# wattcher_to_rpi.net
KiCad netlist of a schematic drawn in EAGLE
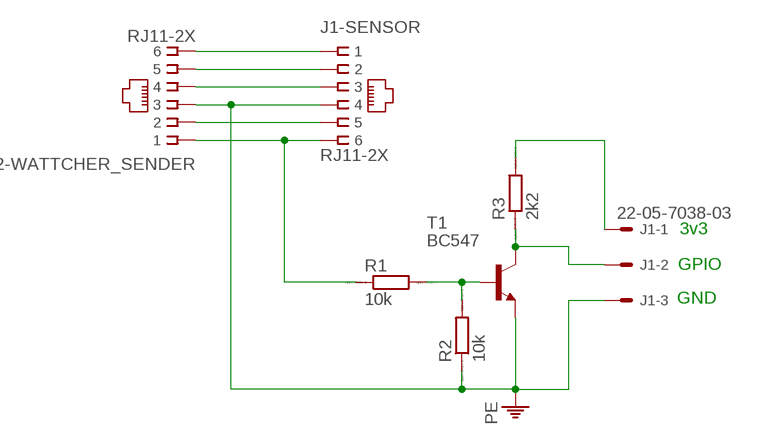
[diagram p0: schematic, sheet 1]

(export (version "E")
  (design (tool "Eeschema 10.0.6"))
  (components
    (comp (ref "J1")
      (value "22-05-7038-03")
      (footprint "eagle-import:7395-03")
      (libsource (lib "eagle-import") (part "22-?-0305-7038"))
    )
    (comp (ref "J1-SENSOR")
      (value "RJ11-2X")
      (footprint "eagle-import:RJ11-NO_SHIELD")
      (libsource (lib "eagle-import") (part "RJ11-2X"))
    )
    (comp (ref "J2-WATTCHER_SENDER")
      (value "RJ11-2X")
      (footprint "eagle-import:RJ11-NO_SHIELD")
      (libsource (lib "eagle-import") (part "RJ11-2X"))
    )
    (comp (ref "R1")
      (value "10k")
      (footprint "eagle-import:0207_7")
      (libsource (lib "eagle-import") (part "R-EU_0207_7"))
    )
    (comp (ref "R2")
      (value "10k")
      (footprint "eagle-import:0207_7")
      (libsource (lib "eagle-import") (part "R-EU_0207_7"))
    )
    (comp (ref "R3")
      (value "2k2")
      (footprint "eagle-import:0207_7")
      (libsource (lib "eagle-import") (part "R-EU_0207_7"))
    )
    (comp (ref "T1")
      (value "BC547")
      (footprint "eagle-import:TO92")
      (libsource (lib "eagle-import") (part "BC547"))
    )
  )
  (nets
    (net (code "1") (name "Net-(J1-SENSOR-Pad1)") (class "Default")
      (node (ref "J1-SENSOR") (pin "1") (pinfunction "1_1") (pintype "passive"))
      (node (ref "J2-WATTCHER_SENDER") (pin "6") (pinfunction "6_6") (pintype "passive"))
    )
    (net (code "2") (name "Net-(J1-SENSOR-Pad2)") (class "Default")
      (node (ref "J1-SENSOR") (pin "2") (pinfunction "2_2") (pintype "passive"))
      (node (ref "J2-WATTCHER_SENDER") (pin "5") (pinfunction "5_5") (pintype "passive"))
    )
    (net (code "3") (name "Net-(J1-SENSOR-Pad3)") (class "Default")
      (node (ref "J1-SENSOR") (pin "3") (pinfunction "3_3") (pintype "passive"))
      (node (ref "J2-WATTCHER_SENDER") (pin "4") (pinfunction "4_4") (pintype "passive"))
    )
    (net (code "4") (name "Net-(J1-SENSOR-Pad5)") (class "Default")
      (node (ref "J1-SENSOR") (pin "5") (pinfunction "5_5") (pintype "passive"))
      (node (ref "J2-WATTCHER_SENDER") (pin "2") (pinfunction "2_2") (pintype "passive"))
    )
    (net (code "5") (name "Net-(J1-SENSOR-Pad6)") (class "Default")
      (node (ref "J1-SENSOR") (pin "6") (pinfunction "6_6") (pintype "passive"))
      (node (ref "J2-WATTCHER_SENDER") (pin "1") (pinfunction "1_1") (pintype "passive"))
      (node (ref "R1") (pin "1") (pinfunction "1_1") (pintype "passive"))
    )
    (net (code "6") (name "Net-(J1A-S)") (class "Default")
      (node (ref "J1") (pin "1") (pinfunction "S_1") (pintype "passive"))
      (node (ref "R3") (pin "2") (pinfunction "2_2") (pintype "passive"))
    )
    (net (code "7") (name "Net-(J1B-S)") (class "Default")
      (node (ref "J1") (pin "2") (pinfunction "S_2") (pintype "passive"))
      (node (ref "R3") (pin "1") (pinfunction "1_1") (pintype "passive"))
      (node (ref "T1") (pin "3") (pinfunction "C_3") (pintype "passive"))
    )
    (net (code "8") (name "Net-(T1-B)") (class "Default")
      (node (ref "R1") (pin "2") (pinfunction "2_2") (pintype "passive"))
      (node (ref "R2") (pin "2") (pinfunction "2_2") (pintype "passive"))
      (node (ref "T1") (pin "2") (pinfunction "B_2") (pintype "passive"))
    )
    (net (code "9") (name "PE") (class "Default")
      (node (ref "J1") (pin "3") (pinfunction "S_3") (pintype "passive"))
      (node (ref "J1-SENSOR") (pin "4") (pinfunction "4_4") (pintype "passive"))
      (node (ref "J2-WATTCHER_SENDER") (pin "3") (pinfunction "3_3") (pintype "passive"))
      (node (ref "R2") (pin "1") (pinfunction "1_1") (pintype "passive"))
      (node (ref "T1") (pin "1") (pinfunction "E_1") (pintype "passive"))
    )
  )
)
